# displayconnector.net
KiCad netlist of a schematic drawn in EAGLE
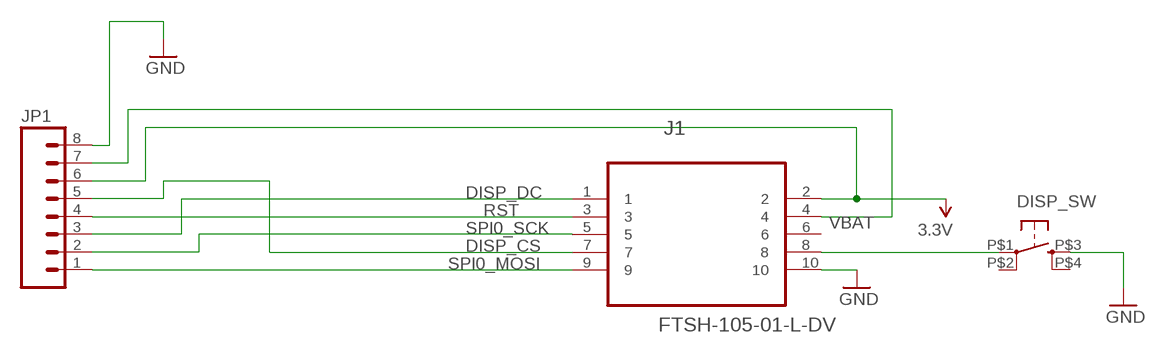
[diagram p0: schematic, sheet 1]

(export (version "E")
  (design (tool "Eeschema 10.0.6"))
  (components
    (comp (ref "DISP_SW")
      (value "TAC_SWITCHKSA_SEALED")
      (footprint "eagle-import:KSA_SEALED_TAC_SWITCH")
      (libsource (lib "eagle-import") (part "TAC_SWITCHKSA_SEALED"))
    )
    (comp (ref "J1")
      (value "FTSH-105-01-L-DV")
      (footprint "eagle-import:SAMTEC_FTSH-105-01-L-DV")
      (libsource (lib "eagle-import") (part "FTSH-105-01-L-DV"))
    )
    (comp (ref "JP1")
      (value "M08LOCK_LONGPADS")
      (footprint "eagle-import:1X08_LOCK_LONGPADS")
      (libsource (lib "eagle-import") (part "M08LOCK_LONGPADS"))
    )
  )
  (nets
    (net (code "1") (name "/DISP_CS") (class "Default")
      (node (ref "J1") (pin "7") (pinfunction "7_7") (pintype "passive"))
      (node (ref "JP1") (pin "5") (pinfunction "5_5") (pintype "passive"))
    )
    (net (code "2") (name "/DISP_DC") (class "Default")
      (node (ref "J1") (pin "1") (pinfunction "1_1") (pintype "passive"))
      (node (ref "JP1") (pin "3") (pinfunction "3_3") (pintype "passive"))
    )
    (net (code "3") (name "/RST") (class "Default")
      (node (ref "J1") (pin "3") (pinfunction "3_3") (pintype "passive"))
      (node (ref "JP1") (pin "4") (pinfunction "4_4") (pintype "passive"))
    )
    (net (code "4") (name "/SPI0_MOSI") (class "Default")
      (node (ref "J1") (pin "9") (pinfunction "9_9") (pintype "passive"))
      (node (ref "JP1") (pin "1") (pinfunction "1_1") (pintype "passive"))
    )
    (net (code "5") (name "/SPI0_SCK") (class "Default")
      (node (ref "J1") (pin "5") (pinfunction "5_5") (pintype "passive"))
      (node (ref "JP1") (pin "2") (pinfunction "2_2") (pintype "passive"))
    )
    (net (code "6") (name "/VBAT") (class "Default")
      (node (ref "J1") (pin "4") (pinfunction "4_4") (pintype "passive"))
      (node (ref "JP1") (pin "7") (pinfunction "7_7") (pintype "passive"))
    )
    (net (code "7") (name "3.3V") (class "Default")
      (node (ref "J1") (pin "2") (pinfunction "2_2") (pintype "passive"))
      (node (ref "JP1") (pin "6") (pinfunction "6_6") (pintype "passive"))
    )
    (net (code "8") (name "GND") (class "Default")
      (node (ref "DISP_SW") (pin "P$3") (pinfunction "3_P$3") (pintype "passive"))
      (node (ref "J1") (pin "10") (pinfunction "10_10") (pintype "passive"))
      (node (ref "JP1") (pin "8") (pinfunction "8_8") (pintype "passive"))
    )
    (net (code "9") (name "Net-(DISP_SW-1)") (class "Default")
      (node (ref "DISP_SW") (pin "P$1") (pinfunction "1_P$1") (pintype "passive"))
      (node (ref "J1") (pin "8") (pinfunction "8_8") (pintype "passive"))
    )
    (net (code "10") (name "unconnected-(DISP_SW-2-PadP$2)") (class "Default")
      (node (ref "DISP_SW") (pin "P$2") (pinfunction "2_P$2") (pintype "passive"))
    )
    (net (code "11") (name "unconnected-(DISP_SW-4-PadP$4)") (class "Default")
      (node (ref "DISP_SW") (pin "P$4") (pinfunction "4_P$4") (pintype "passive"))
    )
    (net (code "12") (name "unconnected-(J1-Pad6)") (class "Default")
      (node (ref "J1") (pin "6") (pinfunction "6_6") (pintype "passive"))
    )
  )
)
